# openLRSminiRX.net
KiCad netlist of a schematic drawn in EAGLE
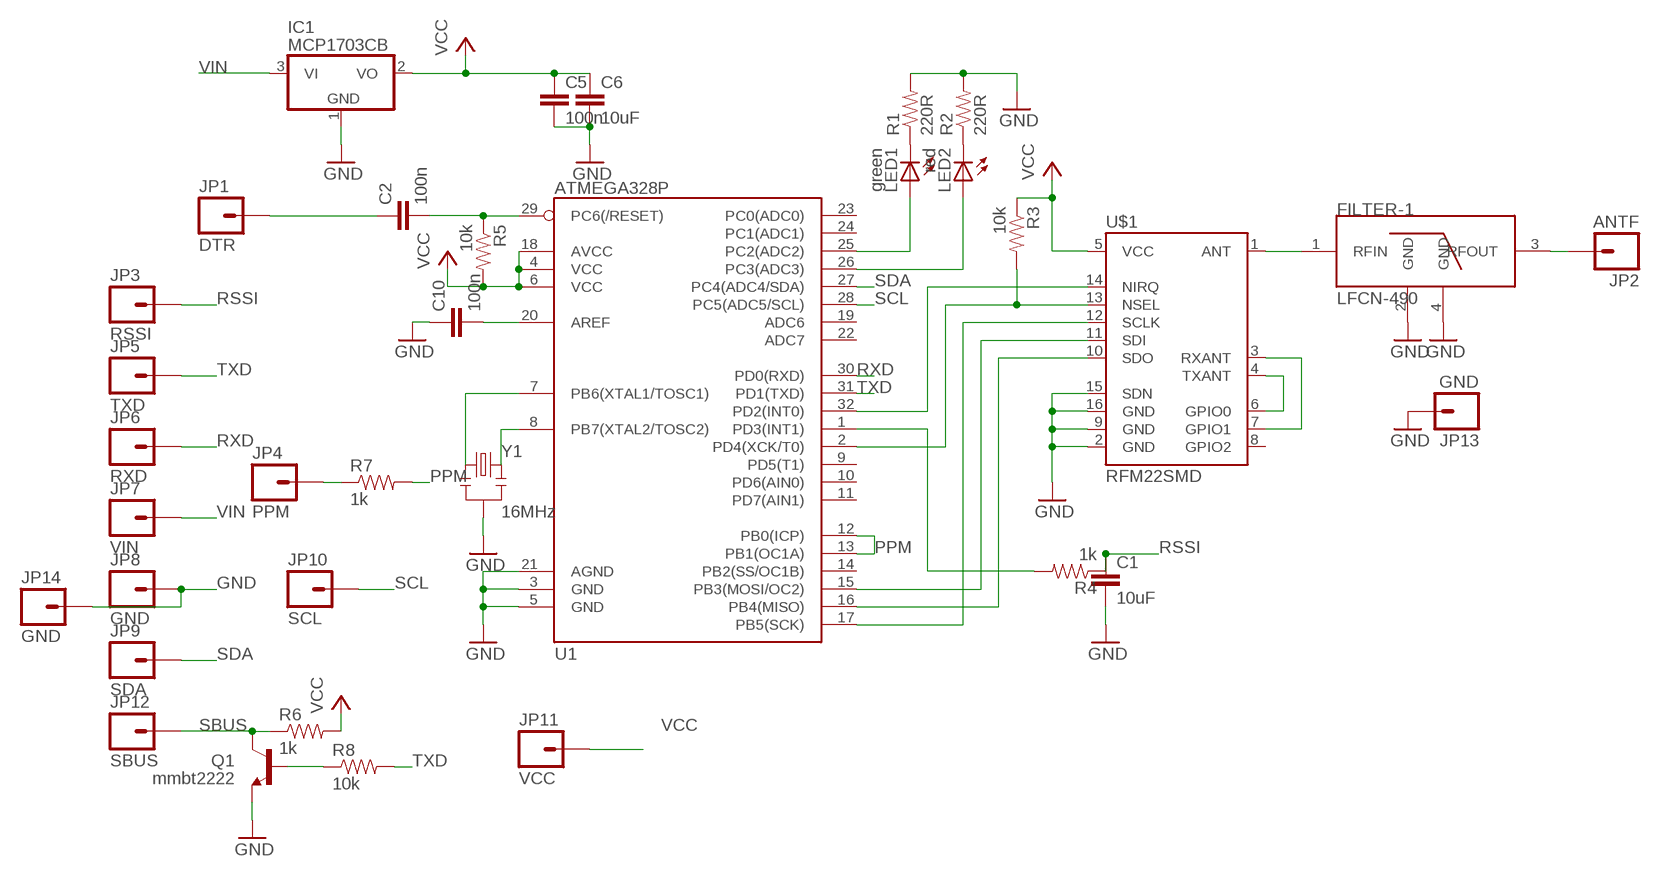
[diagram p0: schematic, sheet 1]

(export (version "E")
  (design (tool "Eeschema 10.0.6"))
  (components
    (comp (ref "C1")
      (value "10uF")
      (footprint "eagle-import:0805")
      (libsource (lib "eagle-import") (part "CAP0805"))
    )
    (comp (ref "C2")
      (value "100n")
      (footprint "eagle-import:0805")
      (libsource (lib "eagle-import") (part "CAP0805"))
    )
    (comp (ref "C5")
      (value "100n")
      (footprint "eagle-import:0805")
      (libsource (lib "eagle-import") (part "CAP0805"))
    )
    (comp (ref "C6")
      (value "10uF")
      (footprint "eagle-import:0805")
      (libsource (lib "eagle-import") (part "CAP0805"))
    )
    (comp (ref "C10")
      (value "100n")
      (footprint "eagle-import:0805")
      (libsource (lib "eagle-import") (part "CAP0805"))
    )
    (comp (ref "FILTER-1")
      (value "LFCN-490")
      (footprint "eagle-import:FV1206")
      (libsource (lib "eagle-import") (part "LFCN-490"))
    )
    (comp (ref "IC1")
      (value "MCP1703CB")
      (footprint "eagle-import:SOT23")
      (libsource (lib "eagle-import") (part "MCP1703CB"))
    )
    (comp (ref "JP1")
      (value "DTR")
      (footprint "eagle-import:1X01")
      (libsource (lib "eagle-import") (part "M01PTH"))
    )
    (comp (ref "JP2")
      (value "ANTF")
      (footprint "eagle-import:1X01")
      (libsource (lib "eagle-import") (part "M01PTH"))
    )
    (comp (ref "JP3")
      (value "RSSI")
      (footprint "eagle-import:1X01")
      (libsource (lib "eagle-import") (part "M01PTH"))
    )
    (comp (ref "JP4")
      (value "PPM")
      (footprint "eagle-import:1X01")
      (libsource (lib "eagle-import") (part "M01PTH"))
    )
    (comp (ref "JP5")
      (value "TXD")
      (footprint "eagle-import:1X01")
      (libsource (lib "eagle-import") (part "M01PTH"))
    )
    (comp (ref "JP6")
      (value "RXD")
      (footprint "eagle-import:1X01")
      (libsource (lib "eagle-import") (part "M01PTH"))
    )
    (comp (ref "JP7")
      (value "VIN")
      (footprint "eagle-import:1X01")
      (libsource (lib "eagle-import") (part "M01PTH"))
    )
    (comp (ref "JP8")
      (value "GND")
      (footprint "eagle-import:1X01")
      (libsource (lib "eagle-import") (part "M01PTH"))
    )
    (comp (ref "JP9")
      (value "SDA")
      (footprint "eagle-import:1X01")
      (libsource (lib "eagle-import") (part "M01PTH"))
    )
    (comp (ref "JP10")
      (value "SCL")
      (footprint "eagle-import:1X01")
      (libsource (lib "eagle-import") (part "M01PTH"))
    )
    (comp (ref "JP11")
      (value "VCC")
      (footprint "eagle-import:1X01")
      (libsource (lib "eagle-import") (part "M01PTH"))
    )
    (comp (ref "JP12")
      (value "SBUS")
      (footprint "eagle-import:1X01")
      (libsource (lib "eagle-import") (part "M01PTH"))
    )
    (comp (ref "JP13")
      (value "GND")
      (footprint "eagle-import:1X01")
      (libsource (lib "eagle-import") (part "M01PTH"))
    )
    (comp (ref "JP14")
      (value "GND")
      (footprint "eagle-import:1X01")
      (libsource (lib "eagle-import") (part "M01PTH"))
    )
    (comp (ref "LED1")
      (value "green")
      (footprint "eagle-import:SML0805")
      (libsource (lib "eagle-import") (part "LEDSML0805"))
    )
    (comp (ref "LED2")
      (value "red")
      (footprint "eagle-import:SML0805")
      (libsource (lib "eagle-import") (part "LEDSML0805"))
    )
    (comp (ref "Q1")
      (value "mmbt2222")
      (footprint "eagle-import:SOT23")
      (libsource (lib "eagle-import") (part "TRANSISTOR_NPNSOT23"))
    )
    (comp (ref "R1")
      (value "220R")
      (footprint "eagle-import:0805")
      (libsource (lib "eagle-import") (part "RESISTOR0805-RES"))
    )
    (comp (ref "R2")
      (value "220R")
      (footprint "eagle-import:0805")
      (libsource (lib "eagle-import") (part "RESISTOR0805-RES"))
    )
    (comp (ref "R3")
      (value "10k")
      (footprint "eagle-import:0805")
      (libsource (lib "eagle-import") (part "RESISTOR0805-RES"))
    )
    (comp (ref "R4")
      (value "1k")
      (footprint "eagle-import:0805")
      (libsource (lib "eagle-import") (part "RESISTOR0805-RES"))
    )
    (comp (ref "R5")
      (value "10k")
      (footprint "eagle-import:0805")
      (libsource (lib "eagle-import") (part "RESISTOR0805-RES"))
    )
    (comp (ref "R6")
      (value "1k")
      (footprint "eagle-import:0805")
      (libsource (lib "eagle-import") (part "RESISTOR0805-RES"))
    )
    (comp (ref "R7")
      (value "1k")
      (footprint "eagle-import:0805")
      (libsource (lib "eagle-import") (part "RESISTOR0805-RES"))
    )
    (comp (ref "R8")
      (value "10k")
      (footprint "eagle-import:0805")
      (libsource (lib "eagle-import") (part "RESISTOR0805-RES"))
    )
    (comp (ref "U$1")
      (value "RFM22SMD")
      (footprint "eagle-import:RFM22-XXX-S2")
      (libsource (lib "eagle-import") (part "RFM22SMD"))
    )
    (comp (ref "U1")
      (value "ATMEGA328P")
      (footprint "eagle-import:TQFP32-08")
      (libsource (lib "eagle-import") (part "ATMEGA328_SMT"))
    )
    (comp (ref "Y1")
      (value "16MHz")
      (footprint "eagle-import:RESONATOR-SMD")
      (libsource (lib "eagle-import") (part "RESONATOR16MHZ"))
    )
  )
  (nets
    (net (code "1") (name "/PPM") (class "Default")
      (node (ref "R7") (pin "2") (pinfunction "2_2") (pintype "passive"))
      (node (ref "U1") (pin "12") (pinfunction "PB0(ICP)_12") (pintype "bidirectional"))
      (node (ref "U1") (pin "13") (pinfunction "PB1(OC1A)_13") (pintype "bidirectional"))
    )
    (net (code "2") (name "/RSSI") (class "Default")
      (node (ref "C1") (pin "1") (pinfunction "1_1") (pintype "passive"))
      (node (ref "JP3") (pin "1") (pinfunction "1_1") (pintype "passive"))
      (node (ref "R4") (pin "1") (pinfunction "1_1") (pintype "passive"))
    )
    (net (code "3") (name "/RXD") (class "Default")
      (node (ref "JP6") (pin "1") (pinfunction "1_1") (pintype "passive"))
      (node (ref "U1") (pin "30") (pinfunction "PD0(RXD)_30") (pintype "bidirectional"))
    )
    (net (code "4") (name "/SBUS") (class "Default")
      (node (ref "JP12") (pin "1") (pinfunction "1_1") (pintype "passive"))
      (node (ref "Q1") (pin "3") (pinfunction "C_3") (pintype "passive"))
      (node (ref "R6") (pin "1") (pinfunction "1_1") (pintype "passive"))
    )
    (net (code "5") (name "/SCL") (class "Default")
      (node (ref "JP10") (pin "1") (pinfunction "1_1") (pintype "passive"))
      (node (ref "U1") (pin "28") (pinfunction "PC5(ADC5/SCL)_28") (pintype "bidirectional"))
    )
    (net (code "6") (name "/SDA") (class "Default")
      (node (ref "JP9") (pin "1") (pinfunction "1_1") (pintype "passive"))
      (node (ref "U1") (pin "27") (pinfunction "PC4(ADC4/SDA)_27") (pintype "bidirectional"))
    )
    (net (code "7") (name "/TXD") (class "Default")
      (node (ref "JP5") (pin "1") (pinfunction "1_1") (pintype "passive"))
      (node (ref "R8") (pin "2") (pinfunction "2_2") (pintype "passive"))
      (node (ref "U1") (pin "31") (pinfunction "PD1(TXD)_31") (pintype "bidirectional"))
    )
    (net (code "8") (name "/VIN") (class "Default")
      (node (ref "IC1") (pin "3") (pinfunction "VI_3") (pintype "input"))
      (node (ref "JP7") (pin "1") (pinfunction "1_1") (pintype "passive"))
    )
    (net (code "9") (name "GND") (class "Default")
      (node (ref "C1") (pin "2") (pinfunction "2_2") (pintype "passive"))
      (node (ref "C10") (pin "1") (pinfunction "1_1") (pintype "passive"))
      (node (ref "C5") (pin "2") (pinfunction "2_2") (pintype "passive"))
      (node (ref "C6") (pin "2") (pinfunction "2_2") (pintype "passive"))
      (node (ref "FILTER-1") (pin "2") (pinfunction "GND_2") (pintype "power_in"))
      (node (ref "FILTER-1") (pin "4") (pinfunction "GND_4") (pintype "power_in"))
      (node (ref "IC1") (pin "1") (pinfunction "GND_1") (pintype "passive"))
      (node (ref "JP13") (pin "1") (pinfunction "1_1") (pintype "passive"))
      (node (ref "JP14") (pin "1") (pinfunction "1_1") (pintype "passive"))
      (node (ref "JP8") (pin "1") (pinfunction "1_1") (pintype "passive"))
      (node (ref "Q1") (pin "2") (pinfunction "E_2") (pintype "passive"))
      (node (ref "R1") (pin "2") (pinfunction "2_2") (pintype "passive"))
      (node (ref "R2") (pin "2") (pinfunction "2_2") (pintype "passive"))
      (node (ref "U$1") (pin "15") (pinfunction "SDN_15") (pintype "input"))
      (node (ref "U$1") (pin "16") (pinfunction "GND_16") (pintype "power_in"))
      (node (ref "U$1") (pin "2") (pinfunction "GND_2") (pintype "power_in"))
      (node (ref "U$1") (pin "9") (pinfunction "GND_9") (pintype "power_in"))
      (node (ref "U1") (pin "21") (pinfunction "AGND_21") (pintype "bidirectional"))
      (node (ref "U1") (pin "3") (pinfunction "GND_3") (pintype "bidirectional"))
      (node (ref "U1") (pin "5") (pinfunction "GND_5") (pintype "bidirectional"))
      (node (ref "Y1") (pin "2") (pinfunction "2_2") (pintype "passive"))
    )
    (net (code "10") (name "Net-(C2-Pad1)") (class "Default")
      (node (ref "C2") (pin "1") (pinfunction "1_1") (pintype "passive"))
      (node (ref "JP1") (pin "1") (pinfunction "1_1") (pintype "passive"))
    )
    (net (code "11") (name "Net-(FILTER-1-RFIN)") (class "Default")
      (node (ref "FILTER-1") (pin "1") (pinfunction "RFIN_1") (pintype "input"))
      (node (ref "U$1") (pin "1") (pinfunction "ANT_1") (pintype "bidirectional"))
    )
    (net (code "12") (name "Net-(FILTER-1-RFOUT)") (class "Default")
      (node (ref "FILTER-1") (pin "3") (pinfunction "RFOUT_3") (pintype "output"))
      (node (ref "JP2") (pin "1") (pinfunction "1_1") (pintype "passive"))
    )
    (net (code "13") (name "Net-(JP4-Pad1)") (class "Default")
      (node (ref "JP4") (pin "1") (pinfunction "1_1") (pintype "passive"))
      (node (ref "R7") (pin "1") (pinfunction "1_1") (pintype "passive"))
    )
    (net (code "14") (name "Net-(LED1-PadC)") (class "Default")
      (node (ref "LED1") (pin "C") (pinfunction "C_C") (pintype "passive"))
      (node (ref "R1") (pin "1") (pinfunction "1_1") (pintype "passive"))
    )
    (net (code "15") (name "Net-(LED2-PadC)") (class "Default")
      (node (ref "LED2") (pin "C") (pinfunction "C_C") (pintype "passive"))
      (node (ref "R2") (pin "1") (pinfunction "1_1") (pintype "passive"))
    )
    (net (code "16") (name "Net-(Q1-B)") (class "Default")
      (node (ref "Q1") (pin "1") (pinfunction "B_1") (pintype "passive"))
      (node (ref "R8") (pin "1") (pinfunction "1_1") (pintype "passive"))
    )
    (net (code "17") (name "Net-(U$1-GPIO0)") (class "Default")
      (node (ref "U$1") (pin "4") (pinfunction "TXANT_4") (pintype "input"))
      (node (ref "U$1") (pin "6") (pinfunction "GPIO0_6") (pintype "bidirectional"))
    )
    (net (code "18") (name "Net-(U$1-GPIO1)") (class "Default")
      (node (ref "U$1") (pin "3") (pinfunction "RXANT_3") (pintype "input"))
      (node (ref "U$1") (pin "7") (pinfunction "GPIO1_7") (pintype "bidirectional"))
    )
    (net (code "19") (name "Net-(U$1-NIRQ)") (class "Default")
      (node (ref "U$1") (pin "14") (pinfunction "NIRQ_14") (pintype "output"))
      (node (ref "U1") (pin "32") (pinfunction "PD2(INT0)_32") (pintype "bidirectional"))
    )
    (net (code "20") (name "Net-(U$1-NSEL)") (class "Default")
      (node (ref "R3") (pin "2") (pinfunction "2_2") (pintype "passive"))
      (node (ref "U$1") (pin "13") (pinfunction "NSEL_13") (pintype "input"))
      (node (ref "U1") (pin "2") (pinfunction "PD4(XCK/T0)_2") (pintype "bidirectional"))
    )
    (net (code "21") (name "Net-(U$1-SCLK)") (class "Default")
      (node (ref "U$1") (pin "12") (pinfunction "SCLK_12") (pintype "input"))
      (node (ref "U1") (pin "17") (pinfunction "PB5(SCK)_17") (pintype "bidirectional"))
    )
    (net (code "22") (name "Net-(U$1-SDI)") (class "Default")
      (node (ref "U$1") (pin "11") (pinfunction "SDI_11") (pintype "input"))
      (node (ref "U1") (pin "15") (pinfunction "PB3(MOSI/OC2)_15") (pintype "bidirectional"))
    )
    (net (code "23") (name "Net-(U$1-SDO)") (class "Default")
      (node (ref "U$1") (pin "10") (pinfunction "SDO_10") (pintype "output"))
      (node (ref "U1") (pin "16") (pinfunction "PB4(MISO)_16") (pintype "bidirectional"))
    )
    (net (code "24") (name "Net-(U1-AREF)") (class "Default")
      (node (ref "C10") (pin "2") (pinfunction "2_2") (pintype "passive"))
      (node (ref "U1") (pin "20") (pinfunction "AREF_20") (pintype "bidirectional"))
    )
    (net (code "25") (name "Net-(U1-PB6(XTAL1{slash}TOSC1))") (class "Default")
      (node (ref "U1") (pin "7") (pinfunction "PB6(XTAL1/TOSC1)_7") (pintype "bidirectional"))
      (node (ref "Y1") (pin "1") (pinfunction "1_1") (pintype "passive"))
    )
    (net (code "26") (name "Net-(U1-PB7(XTAL2{slash}TOSC2))") (class "Default")
      (node (ref "U1") (pin "8") (pinfunction "PB7(XTAL2/TOSC2)_8") (pintype "bidirectional"))
      (node (ref "Y1") (pin "3") (pinfunction "3_3") (pintype "passive"))
    )
    (net (code "27") (name "Net-(U1-PC2(ADC2))") (class "Default")
      (node (ref "LED1") (pin "A") (pinfunction "A_A") (pintype "passive"))
      (node (ref "U1") (pin "25") (pinfunction "PC2(ADC2)_25") (pintype "bidirectional"))
    )
    (net (code "28") (name "Net-(U1-PC3(ADC3))") (class "Default")
      (node (ref "LED2") (pin "A") (pinfunction "A_A") (pintype "passive"))
      (node (ref "U1") (pin "26") (pinfunction "PC3(ADC3)_26") (pintype "bidirectional"))
    )
    (net (code "29") (name "Net-(U1-PC6({slash}RESET))") (class "Default")
      (node (ref "C2") (pin "2") (pinfunction "2_2") (pintype "passive"))
      (node (ref "R5") (pin "1") (pinfunction "1_1") (pintype "passive"))
      (node (ref "U1") (pin "29") (pinfunction "PC6(/RESET)_29") (pintype "bidirectional"))
    )
    (net (code "30") (name "Net-(U1-PD3(INT1))") (class "Default")
      (node (ref "R4") (pin "2") (pinfunction "2_2") (pintype "passive"))
      (node (ref "U1") (pin "1") (pinfunction "PD3(INT1)_1") (pintype "bidirectional"))
    )
    (net (code "31") (name "VCC") (class "Default")
      (node (ref "C5") (pin "1") (pinfunction "1_1") (pintype "passive"))
      (node (ref "C6") (pin "1") (pinfunction "1_1") (pintype "passive"))
      (node (ref "IC1") (pin "2") (pinfunction "VO_2") (pintype "passive"))
      (node (ref "JP11") (pin "1") (pinfunction "1_1") (pintype "passive"))
      (node (ref "R3") (pin "1") (pinfunction "1_1") (pintype "passive"))
      (node (ref "R5") (pin "2") (pinfunction "2_2") (pintype "passive"))
      (node (ref "R6") (pin "2") (pinfunction "2_2") (pintype "passive"))
      (node (ref "U$1") (pin "5") (pinfunction "VCC_5") (pintype "bidirectional"))
      (node (ref "U1") (pin "18") (pinfunction "AVCC_18") (pintype "bidirectional"))
      (node (ref "U1") (pin "4") (pinfunction "VCC_4") (pintype "bidirectional"))
      (node (ref "U1") (pin "6") (pinfunction "VCC_6") (pintype "bidirectional"))
    )
    (net (code "32") (name "unconnected-(U$1-GPIO2-Pad8)") (class "Default")
      (node (ref "U$1") (pin "8") (pinfunction "GPIO2_8") (pintype "bidirectional"))
    )
    (net (code "33") (name "unconnected-(U1-ADC6-Pad19)") (class "Default")
      (node (ref "U1") (pin "19") (pinfunction "ADC6_19") (pintype "bidirectional"))
    )
    (net (code "34") (name "unconnected-(U1-ADC7-Pad22)") (class "Default")
      (node (ref "U1") (pin "22") (pinfunction "ADC7_22") (pintype "bidirectional"))
    )
    (net (code "35") (name "unconnected-(U1-PB2(SS{slash}OC1B)-Pad14)") (class "Default")
      (node (ref "U1") (pin "14") (pinfunction "PB2(SS/OC1B)_14") (pintype "bidirectional"))
    )
    (net (code "36") (name "unconnected-(U1-PC0(ADC0)-Pad23)") (class "Default")
      (node (ref "U1") (pin "23") (pinfunction "PC0(ADC0)_23") (pintype "bidirectional"))
    )
    (net (code "37") (name "unconnected-(U1-PC1(ADC1)-Pad24)") (class "Default")
      (node (ref "U1") (pin "24") (pinfunction "PC1(ADC1)_24") (pintype "bidirectional"))
    )
    (net (code "38") (name "unconnected-(U1-PD5(T1)-Pad9)") (class "Default")
      (node (ref "U1") (pin "9") (pinfunction "PD5(T1)_9") (pintype "bidirectional"))
    )
    (net (code "39") (name "unconnected-(U1-PD6(AIN0)-Pad10)") (class "Default")
      (node (ref "U1") (pin "10") (pinfunction "PD6(AIN0)_10") (pintype "bidirectional"))
    )
    (net (code "40") (name "unconnected-(U1-PD7(AIN1)-Pad11)") (class "Default")
      (node (ref "U1") (pin "11") (pinfunction "PD7(AIN1)_11") (pintype "bidirectional"))
    )
  )
)
